# Sheet1.net
KiCad netlist of a schematic drawn in Altium Designer
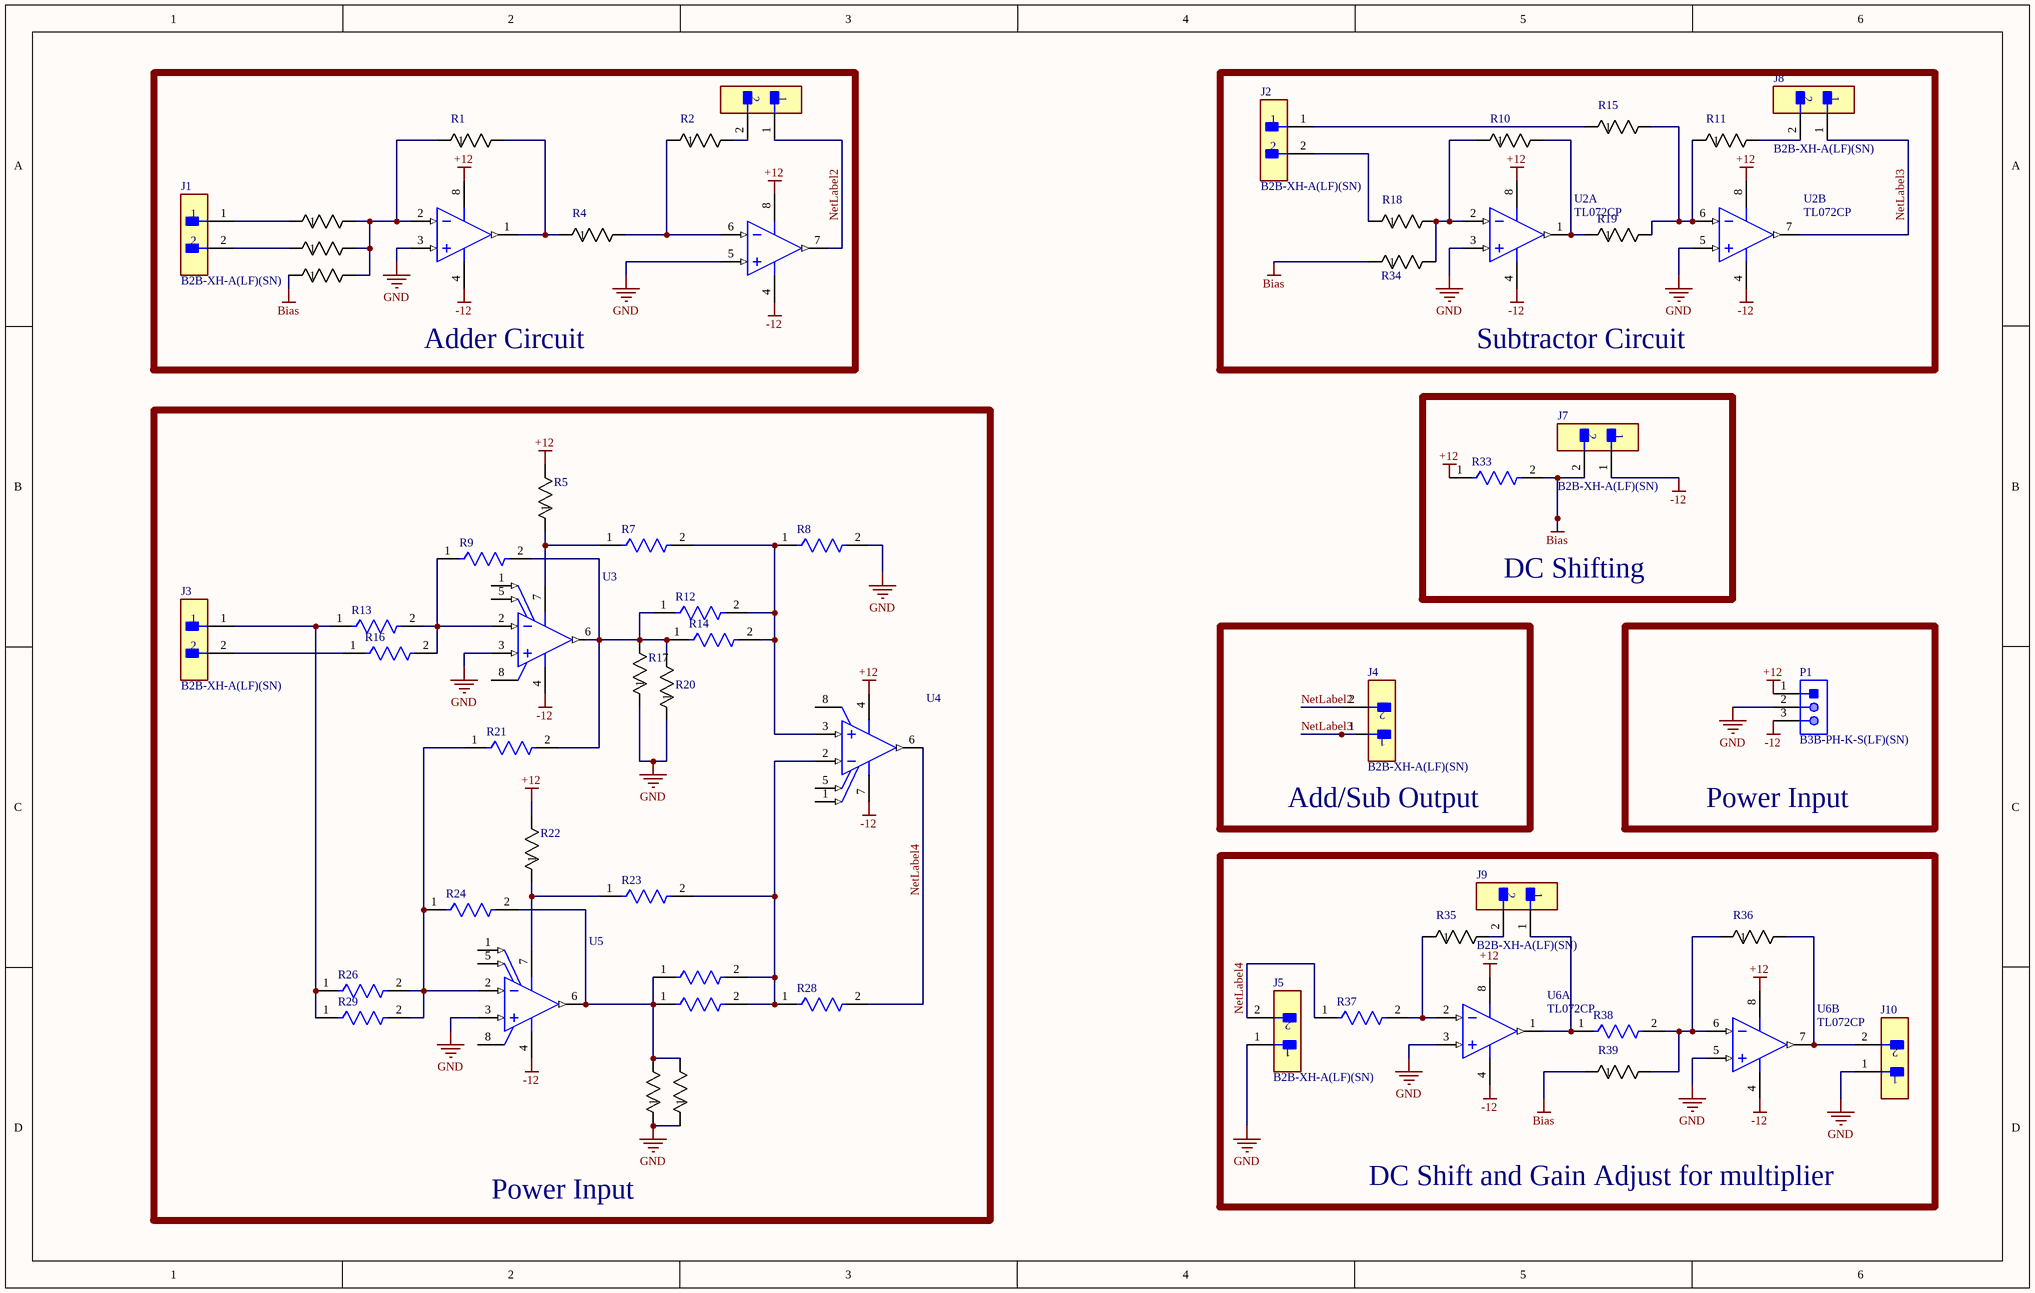
[diagram p0: Sheet1.SchDoc]

(export (version "E")
  (design (tool "Eeschema 10.0.6"))
  (components
    (comp (ref "J1")
      (value "B2B-XH-A(LF)(SN)")
      (footprint "FP-B2B-XH-A_LF_SN-MFG")
      (description "CONN HEADER VERT 2POS 2.5MM")
      (libsource (lib "") (part "3bc925449376181038e59eaffc5286c_1"))
    )
    (comp (ref "J2")
      (value "B2B-XH-A(LF)(SN)")
      (footprint "FP-B2B-XH-A_LF_SN-MFG")
      (description "CONN HEADER VERT 2POS 2.5MM")
      (libsource (lib "") (part "3bc925449376181038e59eaffc5286c_1"))
    )
    (comp (ref "J3")
      (value "B2B-XH-A(LF)(SN)")
      (footprint "FP-B2B-XH-A_LF_SN-MFG")
      (description "CONN HEADER VERT 2POS 2.5MM")
      (libsource (lib "") (part "3bc925449376181038e59eaffc5286c_1"))
    )
    (comp (ref "J4")
      (value "B2B-XH-A(LF)(SN)")
      (footprint "FP-B2B-XH-A_LF_SN-MFG")
      (description "CONN HEADER VERT 2POS 2.5MM")
      (libsource (lib "Altium Content Vault") (part "3bc925449376181038e59eaffc5286c"))
    )
    (comp (ref "J5")
      (value "B2B-XH-A(LF)(SN)")
      (footprint "FP-B2B-XH-A_LF_SN-MFG")
      (description "CONN HEADER VERT 2POS 2.5MM")
      (libsource (lib "Altium Content Vault") (part "3bc925449376181038e59eaffc5286c"))
    )
    (comp (ref "J6")
      (value "B2B-XH-A(LF)(SN)")
      (footprint "FP-B2B-XH-A_LF_SN-MFG")
      (description "CONN HEADER VERT 2POS 2.5MM")
      (libsource (lib "") (part "3bc925449376181038e59eaffc5286c_2"))
    )
    (comp (ref "J7")
      (value "B2B-XH-A(LF)(SN)")
      (footprint "FP-B2B-XH-A_LF_SN-MFG")
      (description "CONN HEADER VERT 2POS 2.5MM")
      (libsource (lib "") (part "3bc925449376181038e59eaffc5286c_2"))
    )
    (comp (ref "J8")
      (value "B2B-XH-A(LF)(SN)")
      (footprint "FP-B2B-XH-A_LF_SN-MFG")
      (description "CONN HEADER VERT 2POS 2.5MM")
      (libsource (lib "") (part "3bc925449376181038e59eaffc5286c_2"))
    )
    (comp (ref "J9")
      (value "B2B-XH-A(LF)(SN)")
      (footprint "FP-B2B-XH-A_LF_SN-MFG")
      (description "CONN HEADER VERT 2POS 2.5MM")
      (libsource (lib "") (part "3bc925449376181038e59eaffc5286c_2"))
    )
    (comp (ref "J10")
      (value "B2B-XH-A(LF)(SN)")
      (footprint "FP-B2B-XH-A_LF_SN-MFG")
      (description "CONN HEADER VERT 2POS 2.5MM")
      (libsource (lib "Altium Content Vault") (part "3bc925449376181038e59eaffc5286c"))
    )
    (comp (ref "P1")
      (value "B3B-PH-K-S(LF)(SN)")
      (footprint "JST-B3B-PH-K-S-3_V")
      (fields (field (name "MANUFACTURER") "JST"))
      (libsource (lib "Altium Content Vault") (part "CN-1P-M-R3"))
    )
    (comp (ref "R1")
      (value "AC03000004701JAC00")
      (footprint "RES_AC03_VIS")
      (fields (field (name "TOLERANCE") "5%"))
      (libsource (lib "Altium Content Vault") (part "AC03000004701JAC00"))
    )
    (comp (ref "R2")
      (value "AC03000004701JAC00")
      (footprint "RES_AC03_VIS")
      (fields (field (name "TOLERANCE") "5%"))
      (libsource (lib "Altium Content Vault") (part "AC03000004701JAC00"))
    )
    (comp (ref "R3")
      (value "AC03000004701JAC00")
      (footprint "RES_AC03_VIS")
      (fields (field (name "TOLERANCE") "5%"))
      (libsource (lib "Altium Content Vault") (part "AC03000004701JAC00"))
    )
    (comp (ref "R4")
      (value "AC03000004701JAC00")
      (footprint "RES_AC03_VIS")
      (fields (field (name "TOLERANCE") "5%"))
      (libsource (lib "Altium Content Vault") (part "AC03000004701JAC00"))
    )
    (comp (ref "R5")
      (value "AC03000002201JAC00")
      (footprint "RES_AC03_VIS")
      (description "AC03000002201JAC00 Resistor, 2.2 kOhm, ± 5%, 3 W, Axial Leaded, Wirewound, General Purpose")
      (fields (field (name "TOLERANCE") "5%"))
      (libsource (lib "Altium Content Vault") (part "AC03000002201JAC00"))
    )
    (comp (ref "R6")
      (value "AC03000004701JAC00")
      (footprint "RES_AC03_VIS")
      (fields (field (name "TOLERANCE") "5%"))
      (libsource (lib "Altium Content Vault") (part "AC03000004701JAC00"))
    )
    (comp (ref "R7")
      (value "PR02000201003JA100")
      (footprint "FP-PR02000201003JA100-MFG")
      (fields (field (name "TOLERANCE") "5%"))
      (libsource (lib "Altium Content Vault") (part "1029c3af85768c4190bb7ad29bc67b5"))
    )
    (comp (ref "R8")
      (value "PR02000201003JA100")
      (footprint "FP-PR02000201003JA100-MFG")
      (fields (field (name "TOLERANCE") "5%"))
      (libsource (lib "Altium Content Vault") (part "1029c3af85768c4190bb7ad29bc67b5"))
    )
    (comp (ref "R9")
      (value "PR02000201003JA100")
      (footprint "FP-PR02000201003JA100-MFG")
      (fields (field (name "TOLERANCE") "5%"))
      (libsource (lib "Altium Content Vault") (part "1029c3af85768c4190bb7ad29bc67b5"))
    )
    (comp (ref "R10")
      (value "AC03000004701JAC00")
      (footprint "RES_AC03_VIS")
      (fields (field (name "TOLERANCE") "5%"))
      (libsource (lib "Altium Content Vault") (part "AC03000004701JAC00"))
    )
    (comp (ref "R11")
      (value "AC03000004701JAC00")
      (footprint "RES_AC03_VIS")
      (fields (field (name "TOLERANCE") "5%"))
      (libsource (lib "Altium Content Vault") (part "AC03000004701JAC00"))
    )
    (comp (ref "R12")
      (value "PR02000201003JA100")
      (footprint "FP-PR02000201003JA100-MFG")
      (fields (field (name "TOLERANCE") "5%"))
      (libsource (lib "Altium Content Vault") (part "1029c3af85768c4190bb7ad29bc67b5"))
    )
    (comp (ref "R13")
      (value "PR02000201003JA100")
      (footprint "FP-PR02000201003JA100-MFG")
      (fields (field (name "TOLERANCE") "5%"))
      (libsource (lib "Altium Content Vault") (part "1029c3af85768c4190bb7ad29bc67b5"))
    )
    (comp (ref "R14")
      (value "PR02000201003JA100")
      (footprint "FP-PR02000201003JA100-MFG")
      (fields (field (name "TOLERANCE") "5%"))
      (libsource (lib "Altium Content Vault") (part "1029c3af85768c4190bb7ad29bc67b5"))
    )
    (comp (ref "R15")
      (value "AC03000004701JAC00")
      (footprint "RES_AC03_VIS")
      (fields (field (name "TOLERANCE") "5%"))
      (libsource (lib "Altium Content Vault") (part "AC03000004701JAC00"))
    )
    (comp (ref "R16")
      (value "PR02000201003JA100")
      (footprint "FP-PR02000201003JA100-MFG")
      (fields (field (name "TOLERANCE") "5%"))
      (libsource (lib "Altium Content Vault") (part "1029c3af85768c4190bb7ad29bc67b5"))
    )
    (comp (ref "R17")
      (value "AC03000004701JAC00")
      (footprint "RES_AC03_VIS")
      (fields (field (name "TOLERANCE") "5%"))
      (libsource (lib "Altium Content Vault") (part "AC03000004701JAC00"))
    )
    (comp (ref "R18")
      (value "AC03000004701JAC00")
      (footprint "RES_AC03_VIS")
      (fields (field (name "TOLERANCE") "5%"))
      (libsource (lib "Altium Content Vault") (part "AC03000004701JAC00"))
    )
    (comp (ref "R19")
      (value "AC03000004701JAC00")
      (footprint "RES_AC03_VIS")
      (fields (field (name "TOLERANCE") "5%"))
      (libsource (lib "Altium Content Vault") (part "AC03000004701JAC00"))
    )
    (comp (ref "R20")
      (value "AC03000004701JAC00")
      (footprint "RES_AC03_VIS")
      (fields (field (name "TOLERANCE") "5%"))
      (libsource (lib "Altium Content Vault") (part "AC03000004701JAC00"))
    )
    (comp (ref "R21")
      (value "PR02000201003JA100")
      (footprint "FP-PR02000201003JA100-MFG")
      (fields (field (name "TOLERANCE") "5%"))
      (libsource (lib "Altium Content Vault") (part "1029c3af85768c4190bb7ad29bc67b5"))
    )
    (comp (ref "R22")
      (value "AC03000002201JAC00")
      (footprint "RES_AC03_VIS")
      (description "AC03000002201JAC00 Resistor, 2.2 kOhm, ± 5%, 3 W, Axial Leaded, Wirewound, General Purpose")
      (fields (field (name "TOLERANCE") "5%"))
      (libsource (lib "Altium Content Vault") (part "AC03000002201JAC00"))
    )
    (comp (ref "R23")
      (value "PR02000201003JA100")
      (footprint "FP-PR02000201003JA100-MFG")
      (fields (field (name "TOLERANCE") "5%"))
      (libsource (lib "Altium Content Vault") (part "1029c3af85768c4190bb7ad29bc67b5"))
    )
    (comp (ref "R24")
      (value "PR02000201003JA100")
      (footprint "FP-PR02000201003JA100-MFG")
      (fields (field (name "TOLERANCE") "5%"))
      (libsource (lib "Altium Content Vault") (part "1029c3af85768c4190bb7ad29bc67b5"))
    )
    (comp (ref "R25")
      (value "PR02000201003JA100")
      (footprint "FP-PR02000201003JA100-MFG")
      (fields (field (name "TOLERANCE") "5%"))
      (libsource (lib "Altium Content Vault") (part "1029c3af85768c4190bb7ad29bc67b5"))
    )
    (comp (ref "R26")
      (value "PR02000201003JA100")
      (footprint "FP-PR02000201003JA100-MFG")
      (fields (field (name "TOLERANCE") "5%"))
      (libsource (lib "Altium Content Vault") (part "1029c3af85768c4190bb7ad29bc67b5"))
    )
    (comp (ref "R27")
      (value "PR02000201003JA100")
      (footprint "FP-PR02000201003JA100-MFG")
      (fields (field (name "TOLERANCE") "5%"))
      (libsource (lib "Altium Content Vault") (part "1029c3af85768c4190bb7ad29bc67b5"))
    )
    (comp (ref "R28")
      (value "PR02000201003JA100")
      (footprint "FP-PR02000201003JA100-MFG")
      (fields (field (name "TOLERANCE") "5%"))
      (libsource (lib "Altium Content Vault") (part "1029c3af85768c4190bb7ad29bc67b5"))
    )
    (comp (ref "R29")
      (value "PR02000201003JA100")
      (footprint "FP-PR02000201003JA100-MFG")
      (fields (field (name "TOLERANCE") "5%"))
      (libsource (lib "Altium Content Vault") (part "1029c3af85768c4190bb7ad29bc67b5"))
    )
    (comp (ref "R30")
      (value "AC03000004701JAC00")
      (footprint "RES_AC03_VIS")
      (fields (field (name "TOLERANCE") "5%"))
      (libsource (lib "Altium Content Vault") (part "AC03000004701JAC00"))
    )
    (comp (ref "R31")
      (value "AC03000004701JAC00")
      (footprint "RES_AC03_VIS")
      (fields (field (name "TOLERANCE") "5%"))
      (libsource (lib "Altium Content Vault") (part "AC03000004701JAC00"))
    )
    (comp (ref "R32")
      (value "AC03000004701JAC00")
      (footprint "RES_AC03_VIS")
      (fields (field (name "TOLERANCE") "5%"))
      (libsource (lib "Altium Content Vault") (part "AC03000004701JAC00"))
    )
    (comp (ref "R33")
      (value "PR02000201003JA100")
      (footprint "FP-PR02000201003JA100-MFG")
      (fields (field (name "TOLERANCE") "5%"))
      (libsource (lib "Altium Content Vault") (part "1029c3af85768c4190bb7ad29bc67b5"))
    )
    (comp (ref "R34")
      (value "AC03000004701JAC00")
      (footprint "RES_AC03_VIS")
      (fields (field (name "TOLERANCE") "5%"))
      (libsource (lib "Altium Content Vault") (part "AC03000004701JAC00"))
    )
    (comp (ref "R35")
      (value "AC03000004701JAC00")
      (footprint "RES_AC03_VIS")
      (fields (field (name "TOLERANCE") "5%"))
      (libsource (lib "Altium Content Vault") (part "AC03000004701JAC00"))
    )
    (comp (ref "R36")
      (value "AC03000004701JAC00")
      (footprint "RES_AC03_VIS")
      (fields (field (name "TOLERANCE") "5%"))
      (libsource (lib "Altium Content Vault") (part "AC03000004701JAC00"))
    )
    (comp (ref "R37")
      (value "PR02000201003JA100")
      (footprint "FP-PR02000201003JA100-MFG")
      (fields (field (name "TOLERANCE") "5%"))
      (libsource (lib "Altium Content Vault") (part "1029c3af85768c4190bb7ad29bc67b5"))
    )
    (comp (ref "R38")
      (value "PR02000201003JA100")
      (footprint "FP-PR02000201003JA100-MFG")
      (fields (field (name "TOLERANCE") "5%"))
      (libsource (lib "Altium Content Vault") (part "1029c3af85768c4190bb7ad29bc67b5"))
    )
    (comp (ref "R39")
      (value "AC03000004701JAC00")
      (footprint "RES_AC03_VIS")
      (fields (field (name "TOLERANCE") "5%"))
      (libsource (lib "Altium Content Vault") (part "AC03000004701JAC00"))
    )
    (comp (ref "U1")
      (value "TL072CP")
      (footprint "P0008A")
      (fields (field (name "MANUFACTURER") "Texas Instruments"))
      (libsource (lib "Altium Content Vault") (part "TI-AMP-D6-2-8_D"))
    )
    (comp (ref "U2")
      (value "TL072CP")
      (footprint "P0008A")
      (fields (field (name "MANUFACTURER") "Texas Instruments"))
      (libsource (lib "Altium Content Vault") (part "TI-AMP-D6-2-8_D"))
    )
    (comp (ref "U3")
      (value "UA741CP")
      (footprint "P0008A")
      (description "General-Purpose Operational Amplifier, 7 to 36 V, 0 to 70 degC, 8-pin DIP (P8), Pb-Free (RoHS)")
      (fields (field (name "MANUFACTURER") "Texas Instruments"))
      (libsource (lib "Altium Content Vault") (part "TI-AMP-S5-2-8"))
    )
    (comp (ref "U4")
      (value "UA741CP")
      (footprint "P0008A")
      (description "General-Purpose Operational Amplifier, 7 to 36 V, 0 to 70 degC, 8-pin DIP (P8), Pb-Free (RoHS)")
      (fields (field (name "MANUFACTURER") "Texas Instruments"))
      (libsource (lib "Altium Content Vault") (part "TI-AMP-S5-2-8"))
    )
    (comp (ref "U5")
      (value "UA741CP")
      (footprint "P0008A")
      (description "General-Purpose Operational Amplifier, 7 to 36 V, 0 to 70 degC, 8-pin DIP (P8), Pb-Free (RoHS)")
      (fields (field (name "MANUFACTURER") "Texas Instruments"))
      (libsource (lib "Altium Content Vault") (part "TI-AMP-S5-2-8"))
    )
    (comp (ref "U6")
      (value "TL072CP")
      (footprint "P0008A")
      (fields (field (name "MANUFACTURER") "Texas Instruments"))
      (libsource (lib "Altium Content Vault") (part "TI-AMP-D6-2-8_D"))
    )
  )
  (nets
    (net (code "1") (name "+12") (class "Default")
      (node (ref "P1") (pin "1") (pinfunction "1_1") (pintype "passive"))
      (node (ref "R22") (pin "2") (pinfunction "2_2") (pintype "passive"))
      (node (ref "R33") (pin "1") (pinfunction "1_1") (pintype "passive"))
      (node (ref "R5") (pin "2") (pinfunction "2_2") (pintype "passive"))
      (node (ref "U1") (pin "8") (pinfunction "VCC+_8") (pintype "power_in"))
      (node (ref "U2") (pin "8") (pinfunction "VCC+_8") (pintype "power_in"))
      (node (ref "U4") (pin "4") (pinfunction "VCC-_4") (pintype "power_in"))
      (node (ref "U6") (pin "8") (pinfunction "VCC+_8") (pintype "power_in"))
    )
    (net (code "2") (name "-12") (class "Default")
      (node (ref "J7") (pin "1") (pinfunction "1_1") (pintype "passive"))
      (node (ref "P1") (pin "3") (pinfunction "3_3") (pintype "passive"))
      (node (ref "U1") (pin "4") (pinfunction "VCC-_4") (pintype "power_in"))
      (node (ref "U2") (pin "4") (pinfunction "VCC-_4") (pintype "power_in"))
      (node (ref "U3") (pin "4") (pinfunction "VCC-_4") (pintype "power_in"))
      (node (ref "U4") (pin "7") (pinfunction "VCC+_7") (pintype "power_in"))
      (node (ref "U5") (pin "4") (pinfunction "VCC-_4") (pintype "power_in"))
      (node (ref "U6") (pin "4") (pinfunction "VCC-_4") (pintype "power_in"))
    )
    (net (code "3") (name "/NetLabel2") (class "Default")
      (node (ref "J4") (pin "2") (pinfunction "2_2") (pintype "passive"))
      (node (ref "J6") (pin "1") (pinfunction "1_1") (pintype "passive"))
      (node (ref "U1") (pin "7") (pinfunction "OUT2_7") (pintype "output"))
    )
    (net (code "4") (name "/NetLabel3") (class "Default")
      (node (ref "J4") (pin "1") (pinfunction "1_1") (pintype "passive"))
      (node (ref "J8") (pin "1") (pinfunction "1_1") (pintype "passive"))
      (node (ref "U2") (pin "7") (pinfunction "OUT2_7") (pintype "output"))
    )
    (net (code "5") (name "/NetLabel4") (class "Default")
      (node (ref "J5") (pin "2") (pinfunction "2_2") (pintype "passive"))
      (node (ref "R28") (pin "2") (pinfunction "2_2") (pintype "passive"))
      (node (ref "R37") (pin "1") (pinfunction "1_1") (pintype "passive"))
      (node (ref "U4") (pin "6") (pinfunction "OUT_6") (pintype "output"))
    )
    (net (code "6") (name "Bias") (class "Default")
      (node (ref "J7") (pin "2") (pinfunction "2_2") (pintype "passive"))
      (node (ref "R32") (pin "1") (pinfunction "1_1") (pintype "passive"))
      (node (ref "R33") (pin "2") (pinfunction "2_2") (pintype "passive"))
      (node (ref "R34") (pin "1") (pinfunction "1_1") (pintype "passive"))
      (node (ref "R39") (pin "1") (pinfunction "1_1") (pintype "passive"))
    )
    (net (code "7") (name "GND") (class "Default")
      (node (ref "J10") (pin "1") (pinfunction "1_1") (pintype "passive"))
      (node (ref "J5") (pin "1") (pinfunction "1_1") (pintype "passive"))
      (node (ref "P1") (pin "2") (pinfunction "2_2") (pintype "passive"))
      (node (ref "R17") (pin "1") (pinfunction "1_1") (pintype "passive"))
      (node (ref "R20") (pin "1") (pinfunction "1_1") (pintype "passive"))
      (node (ref "R30") (pin "1") (pinfunction "1_1") (pintype "passive"))
      (node (ref "R31") (pin "1") (pinfunction "1_1") (pintype "passive"))
      (node (ref "R8") (pin "2") (pinfunction "2_2") (pintype "passive"))
      (node (ref "U1") (pin "3") (pinfunction "IN1+_3") (pintype "input"))
      (node (ref "U1") (pin "5") (pinfunction "IN2+_5") (pintype "input"))
      (node (ref "U2") (pin "3") (pinfunction "IN1+_3") (pintype "input"))
      (node (ref "U2") (pin "5") (pinfunction "IN2+_5") (pintype "input"))
      (node (ref "U3") (pin "3") (pinfunction "IN+_3") (pintype "input"))
      (node (ref "U5") (pin "3") (pinfunction "IN+_3") (pintype "input"))
      (node (ref "U6") (pin "3") (pinfunction "IN1+_3") (pintype "input"))
      (node (ref "U6") (pin "5") (pinfunction "IN2+_5") (pintype "input"))
    )
    (net (code "8") (name "Net-(J1-Pad1)") (class "Default")
      (node (ref "J1") (pin "1") (pinfunction "1_1") (pintype "passive"))
      (node (ref "R3") (pin "1") (pinfunction "1_1") (pintype "passive"))
    )
    (net (code "9") (name "Net-(J1-Pad2)") (class "Default")
      (node (ref "J1") (pin "2") (pinfunction "2_2") (pintype "passive"))
      (node (ref "R6") (pin "1") (pinfunction "1_1") (pintype "passive"))
    )
    (net (code "10") (name "Net-(J2-Pad1)") (class "Default")
      (node (ref "J2") (pin "1") (pinfunction "1_1") (pintype "passive"))
      (node (ref "R15") (pin "1") (pinfunction "1_1") (pintype "passive"))
    )
    (net (code "11") (name "Net-(J2-Pad2)") (class "Default")
      (node (ref "J2") (pin "2") (pinfunction "2_2") (pintype "passive"))
      (node (ref "R18") (pin "1") (pinfunction "1_1") (pintype "passive"))
    )
    (net (code "12") (name "Net-(J3-Pad1)") (class "Default")
      (node (ref "J3") (pin "1") (pinfunction "1_1") (pintype "passive"))
      (node (ref "R13") (pin "1") (pinfunction "1_1") (pintype "passive"))
      (node (ref "R26") (pin "1") (pinfunction "1_1") (pintype "passive"))
      (node (ref "R29") (pin "1") (pinfunction "1_1") (pintype "passive"))
    )
    (net (code "13") (name "Net-(J3-Pad2)") (class "Default")
      (node (ref "J3") (pin "2") (pinfunction "2_2") (pintype "passive"))
      (node (ref "R16") (pin "1") (pinfunction "1_1") (pintype "passive"))
    )
    (net (code "14") (name "Net-(J6-Pad2)") (class "Default")
      (node (ref "J6") (pin "2") (pinfunction "2_2") (pintype "passive"))
      (node (ref "R2") (pin "2") (pinfunction "2_2") (pintype "passive"))
    )
    (net (code "15") (name "Net-(J8-Pad2)") (class "Default")
      (node (ref "J8") (pin "2") (pinfunction "2_2") (pintype "passive"))
      (node (ref "R11") (pin "2") (pinfunction "2_2") (pintype "passive"))
    )
    (net (code "16") (name "Net-(J9-Pad2)") (class "Default")
      (node (ref "J9") (pin "2") (pinfunction "2_2") (pintype "passive"))
      (node (ref "R35") (pin "2") (pinfunction "2_2") (pintype "passive"))
    )
    (net (code "17") (name "Net-(U1A-IN1-)") (class "Default")
      (node (ref "R1") (pin "1") (pinfunction "1_1") (pintype "passive"))
      (node (ref "R3") (pin "2") (pinfunction "2_2") (pintype "passive"))
      (node (ref "R32") (pin "2") (pinfunction "2_2") (pintype "passive"))
      (node (ref "R6") (pin "2") (pinfunction "2_2") (pintype "passive"))
      (node (ref "U1") (pin "2") (pinfunction "IN1-_2") (pintype "input"))
    )
    (net (code "18") (name "Net-(U1A-OUT1)") (class "Default")
      (node (ref "R1") (pin "2") (pinfunction "2_2") (pintype "passive"))
      (node (ref "R4") (pin "1") (pinfunction "1_1") (pintype "passive"))
      (node (ref "U1") (pin "1") (pinfunction "OUT1_1") (pintype "output"))
    )
    (net (code "19") (name "Net-(U1B-IN2-)") (class "Default")
      (node (ref "R2") (pin "1") (pinfunction "1_1") (pintype "passive"))
      (node (ref "R4") (pin "2") (pinfunction "2_2") (pintype "passive"))
      (node (ref "U1") (pin "6") (pinfunction "IN2-_6") (pintype "input"))
    )
    (net (code "20") (name "Net-(U2A-IN1-)") (class "Default")
      (node (ref "R10") (pin "1") (pinfunction "1_1") (pintype "passive"))
      (node (ref "R18") (pin "2") (pinfunction "2_2") (pintype "passive"))
      (node (ref "R34") (pin "2") (pinfunction "2_2") (pintype "passive"))
      (node (ref "U2") (pin "2") (pinfunction "IN1-_2") (pintype "input"))
    )
    (net (code "21") (name "Net-(U2A-OUT1)") (class "Default")
      (node (ref "R10") (pin "2") (pinfunction "2_2") (pintype "passive"))
      (node (ref "R19") (pin "1") (pinfunction "1_1") (pintype "passive"))
      (node (ref "U2") (pin "1") (pinfunction "OUT1_1") (pintype "output"))
    )
    (net (code "22") (name "Net-(U2B-IN2-)") (class "Default")
      (node (ref "R11") (pin "1") (pinfunction "1_1") (pintype "passive"))
      (node (ref "R15") (pin "2") (pinfunction "2_2") (pintype "passive"))
      (node (ref "R19") (pin "2") (pinfunction "2_2") (pintype "passive"))
      (node (ref "U2") (pin "6") (pinfunction "IN2-_6") (pintype "input"))
    )
    (net (code "23") (name "Net-(U3-IN-)") (class "Default")
      (node (ref "R13") (pin "2") (pinfunction "2_2") (pintype "passive"))
      (node (ref "R16") (pin "2") (pinfunction "2_2") (pintype "passive"))
      (node (ref "R9") (pin "1") (pinfunction "1_1") (pintype "passive"))
      (node (ref "U3") (pin "2") (pinfunction "IN-_2") (pintype "input"))
    )
    (net (code "24") (name "Net-(U3-OUT)") (class "Default")
      (node (ref "R12") (pin "1") (pinfunction "1_1") (pintype "passive"))
      (node (ref "R14") (pin "1") (pinfunction "1_1") (pintype "passive"))
      (node (ref "R17") (pin "2") (pinfunction "2_2") (pintype "passive"))
      (node (ref "R20") (pin "2") (pinfunction "2_2") (pintype "passive"))
      (node (ref "R21") (pin "2") (pinfunction "2_2") (pintype "passive"))
      (node (ref "R9") (pin "2") (pinfunction "2_2") (pintype "passive"))
      (node (ref "U3") (pin "6") (pinfunction "OUT_6") (pintype "output"))
    )
    (net (code "25") (name "Net-(U3-VCC+)") (class "Default")
      (node (ref "R5") (pin "1") (pinfunction "1_1") (pintype "passive"))
      (node (ref "R7") (pin "1") (pinfunction "1_1") (pintype "passive"))
      (node (ref "U3") (pin "7") (pinfunction "VCC+_7") (pintype "power_in"))
    )
    (net (code "26") (name "Net-(U4-IN+)") (class "Default")
      (node (ref "R12") (pin "2") (pinfunction "2_2") (pintype "passive"))
      (node (ref "R14") (pin "2") (pinfunction "2_2") (pintype "passive"))
      (node (ref "R7") (pin "2") (pinfunction "2_2") (pintype "passive"))
      (node (ref "R8") (pin "1") (pinfunction "1_1") (pintype "passive"))
      (node (ref "U4") (pin "3") (pinfunction "IN+_3") (pintype "input"))
    )
    (net (code "27") (name "Net-(U4-IN-)") (class "Default")
      (node (ref "R23") (pin "2") (pinfunction "2_2") (pintype "passive"))
      (node (ref "R25") (pin "2") (pinfunction "2_2") (pintype "passive"))
      (node (ref "R27") (pin "2") (pinfunction "2_2") (pintype "passive"))
      (node (ref "R28") (pin "1") (pinfunction "1_1") (pintype "passive"))
      (node (ref "U4") (pin "2") (pinfunction "IN-_2") (pintype "input"))
    )
    (net (code "28") (name "Net-(U5-IN-)") (class "Default")
      (node (ref "R21") (pin "1") (pinfunction "1_1") (pintype "passive"))
      (node (ref "R24") (pin "1") (pinfunction "1_1") (pintype "passive"))
      (node (ref "R26") (pin "2") (pinfunction "2_2") (pintype "passive"))
      (node (ref "R29") (pin "2") (pinfunction "2_2") (pintype "passive"))
      (node (ref "U5") (pin "2") (pinfunction "IN-_2") (pintype "input"))
    )
    (net (code "29") (name "Net-(U5-OUT)") (class "Default")
      (node (ref "R24") (pin "2") (pinfunction "2_2") (pintype "passive"))
      (node (ref "R25") (pin "1") (pinfunction "1_1") (pintype "passive"))
      (node (ref "R27") (pin "1") (pinfunction "1_1") (pintype "passive"))
      (node (ref "R30") (pin "2") (pinfunction "2_2") (pintype "passive"))
      (node (ref "R31") (pin "2") (pinfunction "2_2") (pintype "passive"))
      (node (ref "U5") (pin "6") (pinfunction "OUT_6") (pintype "output"))
    )
    (net (code "30") (name "Net-(U5-VCC+)") (class "Default")
      (node (ref "R22") (pin "1") (pinfunction "1_1") (pintype "passive"))
      (node (ref "R23") (pin "1") (pinfunction "1_1") (pintype "passive"))
      (node (ref "U5") (pin "7") (pinfunction "VCC+_7") (pintype "power_in"))
    )
    (net (code "31") (name "Net-(U6A-IN1-)") (class "Default")
      (node (ref "R35") (pin "1") (pinfunction "1_1") (pintype "passive"))
      (node (ref "R37") (pin "2") (pinfunction "2_2") (pintype "passive"))
      (node (ref "U6") (pin "2") (pinfunction "IN1-_2") (pintype "input"))
    )
    (net (code "32") (name "Net-(U6A-OUT1)") (class "Default")
      (node (ref "J9") (pin "1") (pinfunction "1_1") (pintype "passive"))
      (node (ref "R38") (pin "1") (pinfunction "1_1") (pintype "passive"))
      (node (ref "U6") (pin "1") (pinfunction "OUT1_1") (pintype "output"))
    )
    (net (code "33") (name "Net-(U6B-IN2-)") (class "Default")
      (node (ref "R36") (pin "1") (pinfunction "1_1") (pintype "passive"))
      (node (ref "R38") (pin "2") (pinfunction "2_2") (pintype "passive"))
      (node (ref "R39") (pin "2") (pinfunction "2_2") (pintype "passive"))
      (node (ref "U6") (pin "6") (pinfunction "IN2-_6") (pintype "input"))
    )
    (net (code "34") (name "Net-(U6B-OUT2)") (class "Default")
      (node (ref "J10") (pin "2") (pinfunction "2_2") (pintype "passive"))
      (node (ref "R36") (pin "2") (pinfunction "2_2") (pintype "passive"))
      (node (ref "U6") (pin "7") (pinfunction "OUT2_7") (pintype "output"))
    )
    (net (code "35") (name "unconnected-(U3-NC-Pad8)") (class "Default")
      (node (ref "U3") (pin "8") (pinfunction "NC_8") (pintype "passive"))
    )
    (net (code "36") (name "unconnected-(U3-OFFSET_N1-Pad1)") (class "Default")
      (node (ref "U3") (pin "1") (pinfunction "OFFSET_N1_1") (pintype "input"))
    )
    (net (code "37") (name "unconnected-(U3-OFFSET_N2-Pad5)") (class "Default")
      (node (ref "U3") (pin "5") (pinfunction "OFFSET_N2_5") (pintype "input"))
    )
    (net (code "38") (name "unconnected-(U4-NC-Pad8)") (class "Default")
      (node (ref "U4") (pin "8") (pinfunction "NC_8") (pintype "passive"))
    )
    (net (code "39") (name "unconnected-(U4-OFFSET_N1-Pad1)") (class "Default")
      (node (ref "U4") (pin "1") (pinfunction "OFFSET_N1_1") (pintype "input"))
    )
    (net (code "40") (name "unconnected-(U4-OFFSET_N2-Pad5)") (class "Default")
      (node (ref "U4") (pin "5") (pinfunction "OFFSET_N2_5") (pintype "input"))
    )
    (net (code "41") (name "unconnected-(U5-NC-Pad8)") (class "Default")
      (node (ref "U5") (pin "8") (pinfunction "NC_8") (pintype "passive"))
    )
    (net (code "42") (name "unconnected-(U5-OFFSET_N1-Pad1)") (class "Default")
      (node (ref "U5") (pin "1") (pinfunction "OFFSET_N1_1") (pintype "input"))
    )
    (net (code "43") (name "unconnected-(U5-OFFSET_N2-Pad5)") (class "Default")
      (node (ref "U5") (pin "5") (pinfunction "OFFSET_N2_5") (pintype "input"))
    )
  )
)
